# Connectors.net
KiCad netlist of a schematic drawn in Altium Designer
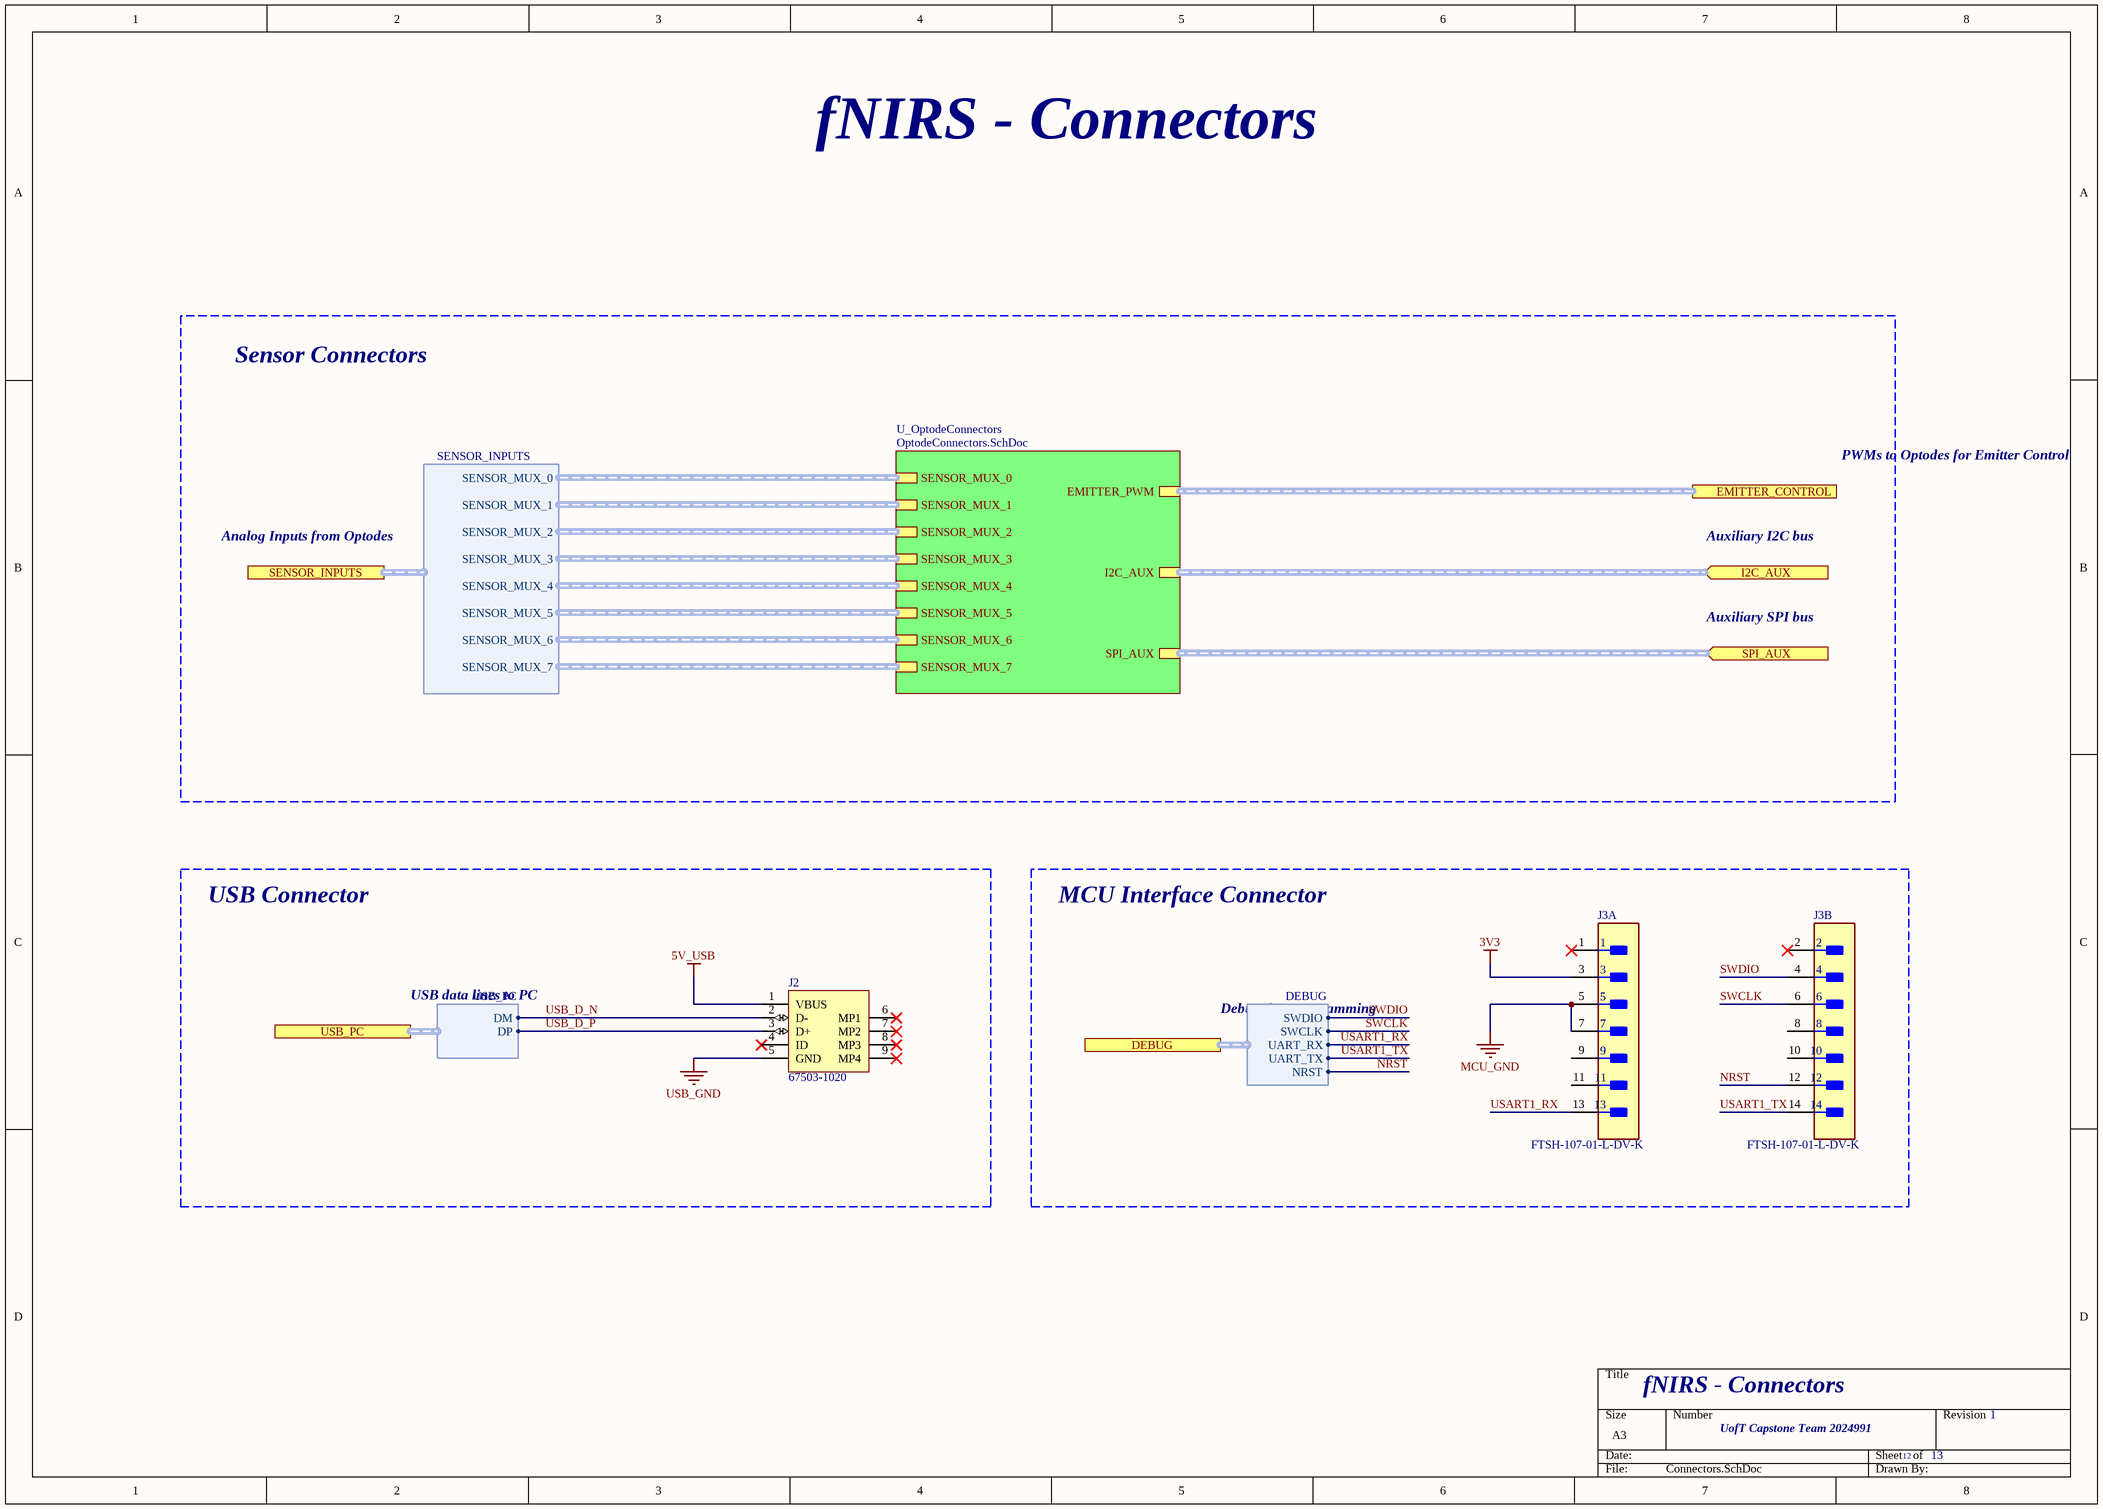
[diagram p0: Connectors.SchDoc]

(export (version "E")
  (design (tool "Eeschema 10.0.6"))
  (components
    (comp (ref "J2")
      (value "67503-1020")
      (footprint "MOLX-67503-1020_V")
      (description "USB, MINI, SMD, RA KME04-USBMU03A01")
      (fields (field (name "MANUFACTURER") "Molex"))
      (libsource (lib "Altium Content Vault") (part "MOLX-67503-1020"))
    )
    (comp (ref "J3")
      (value "FTSH-107-01-L-DV-K")
      (footprint "FP-FTSH-107-01-L-DV-K-MFG")
      (description "CONN HEADER SMD 14POS 1.27MM")
      (libsource (lib "Altium Content Vault") (part "7644e1a88aa4da17242a9b8d8257442"))
    )
  )
  (nets
    (net (code "10") (name "/NRST") (class "Default")
      (node (ref "J3") (pin "12") (pinfunction "12_12") (pintype "passive"))
    )
    (net (code "20") (name "/SWCLK") (class "Default")
      (node (ref "J3") (pin "6") (pinfunction "6_6") (pintype "passive"))
    )
    (net (code "21") (name "/SWDIO") (class "Default")
      (node (ref "J3") (pin "4") (pinfunction "4_4") (pintype "passive"))
    )
    (net (code "22") (name "/USART1_RX") (class "Default")
      (node (ref "J3") (pin "13") (pinfunction "13_13") (pintype "passive"))
    )
    (net (code "23") (name "/USART1_TX") (class "Default")
      (node (ref "J3") (pin "14") (pinfunction "14_14") (pintype "passive"))
    )
    (net (code "24") (name "/USB_D_N") (class "Default")
      (node (ref "J2") (pin "2") (pinfunction "D-_2") (pintype "bidirectional"))
    )
    (net (code "25") (name "/USB_D_P") (class "Default")
      (node (ref "J2") (pin "3") (pinfunction "D+_3") (pintype "bidirectional"))
    )
    (net (code "29") (name "3V3") (class "Default")
      (node (ref "J3") (pin "3") (pinfunction "3_3") (pintype "passive"))
    )
    (net (code "30") (name "5V_USB") (class "Default")
      (node (ref "J2") (pin "1") (pinfunction "VBUS_1") (pintype "power_in"))
    )
    (net (code "31") (name "MCU_GND") (class "Default")
      (node (ref "J3") (pin "5") (pinfunction "5_5") (pintype "passive"))
      (node (ref "J3") (pin "7") (pinfunction "7_7") (pintype "passive"))
    )
    (net (code "32") (name "USB_GND") (class "Default")
      (node (ref "J2") (pin "5") (pinfunction "GND_5") (pintype "power_in"))
    )
    (net (code "33") (name "unconnected-(J2-ID-Pad4)") (class "Default")
      (node (ref "J2") (pin "4") (pinfunction "ID_4") (pintype "passive+no_connect"))
    )
    (net (code "34") (name "unconnected-(J2-MP1-Pad6)") (class "Default")
      (node (ref "J2") (pin "6") (pinfunction "MP1_6") (pintype "passive+no_connect"))
    )
    (net (code "35") (name "unconnected-(J2-MP2-Pad7)") (class "Default")
      (node (ref "J2") (pin "7") (pinfunction "MP2_7") (pintype "passive+no_connect"))
    )
    (net (code "36") (name "unconnected-(J2-MP3-Pad8)") (class "Default")
      (node (ref "J2") (pin "8") (pinfunction "MP3_8") (pintype "passive+no_connect"))
    )
    (net (code "37") (name "unconnected-(J2-MP4-Pad9)") (class "Default")
      (node (ref "J2") (pin "9") (pinfunction "MP4_9") (pintype "passive+no_connect"))
    )
    (net (code "38") (name "unconnected-(J3-Pad1)") (class "Default")
      (node (ref "J3") (pin "1") (pinfunction "1_1") (pintype "passive+no_connect"))
    )
    (net (code "39") (name "unconnected-(J3-Pad2)") (class "Default")
      (node (ref "J3") (pin "2") (pinfunction "2_2") (pintype "passive+no_connect"))
    )
    (net (code "40") (name "unconnected-(J3-Pad8)") (class "Default")
      (node (ref "J3") (pin "8") (pinfunction "8_8") (pintype "passive"))
    )
    (net (code "41") (name "unconnected-(J3-Pad9)") (class "Default")
      (node (ref "J3") (pin "9") (pinfunction "9_9") (pintype "passive"))
    )
    (net (code "42") (name "unconnected-(J3-Pad10)") (class "Default")
      (node (ref "J3") (pin "10") (pinfunction "10_10") (pintype "passive"))
    )
    (net (code "43") (name "unconnected-(J3-Pad11)") (class "Default")
      (node (ref "J3") (pin "11") (pinfunction "11_11") (pintype "passive"))
    )
  )
)
